# Reed_Switch_Input.net
KiCad netlist of a schematic drawn in Altium Designer
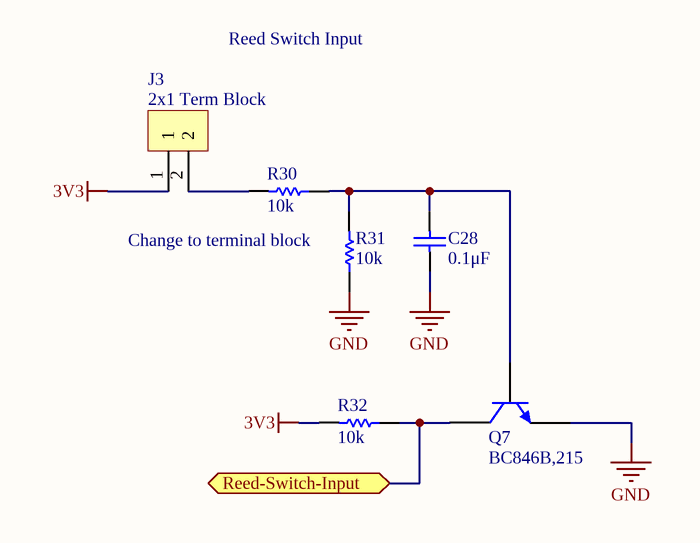
[diagram p0: Reed_Switch_Input.SchDoc]

(export (version "E")
  (design (tool "Eeschema 10.0.6"))
  (components
    (comp (ref "C28")
      (value "0.1μF")
      (footprint "CAPC1608N(0603\")")
      (description "Capacitor, Ceramic, 100V, +/- 10%, 0603 SMD, X7R")
      (fields
        (field (name "MFG") "TDK")
        (field (name "PUBLISHER") "AUVic")
        (field (name "CREATED BY") "Ashwin Sira")
      )
      (libsource (lib "AUVic_Integrated_Library_Capacitors") (part "0.1uF 100V 0603 SMD, Ceramic"))
    )
    (comp (ref "J3")
      (value "2x1 Term Block")
      (footprint "2X1 Terminal Blocks")
      (fields (field (name "MADE BY") "Andy Bates"))
      (libsource (lib "AUVic_Integrated_Library_Connectors") (part "2x1 Terminal Block"))
    )
    (comp (ref "Q7")
      (value "BC846B,215")
      (footprint "SOT-23")
      (description "NPN 65V 100mA 250mW")
      (fields (field (name "PUBLISHER") "Andy Bates"))
      (libsource (lib "AUVic_Integrated_Library_Transistors") (part "BC846B,215"))
    )
    (comp (ref "R30")
      (value "10k")
      (footprint "RESC1608N(0603\")")
      (description "10kR, 1%, 1/10W, 0603 SMD")
      (fields (field (name "MADE BY") "Ashwin Sira"))
      (libsource (lib "AUVic_Integrated_Library_Resistors") (part "10kR, 1%, 1/10W, 0603 SMD"))
    )
    (comp (ref "R31")
      (value "10k")
      (footprint "RESC1608N(0603\")")
      (description "10kR, 1%, 1/10W, 0603 SMD")
      (fields (field (name "MADE BY") "Ashwin Sira"))
      (libsource (lib "AUVic_Integrated_Library_Resistors") (part "10kR, 1%, 1/10W, 0603 SMD"))
    )
    (comp (ref "R32")
      (value "10k")
      (footprint "RESC1608N(0603\")")
      (description "10kR, 1%, 1/10W, 0603 SMD")
      (fields (field (name "MADE BY") "Ashwin Sira"))
      (libsource (lib "AUVic_Integrated_Library_Resistors") (part "10kR, 1%, 1/10W, 0603 SMD"))
    )
  )
  (nets
    (net (code "1") (name "/Reed-Switch-Input") (class "Default")
      (node (ref "Q7") (pin "3") (pinfunction "C_3") (pintype "passive"))
      (node (ref "R32") (pin "1") (pinfunction "1_1") (pintype "passive"))
    )
    (net (code "2") (name "3V3") (class "Default")
      (node (ref "J3") (pin "1") (pinfunction "1_1") (pintype "passive"))
      (node (ref "R32") (pin "2") (pinfunction "2_2") (pintype "passive"))
    )
    (net (code "3") (name "GND") (class "Default")
      (node (ref "C28") (pin "1") (pinfunction "Anode_1") (pintype "passive"))
      (node (ref "Q7") (pin "2") (pinfunction "E_2") (pintype "passive"))
      (node (ref "R31") (pin "1") (pinfunction "1_1") (pintype "passive"))
    )
    (net (code "4") (name "Net-(C28-Cathode)") (class "Default")
      (node (ref "C28") (pin "2") (pinfunction "Cathode_2") (pintype "passive"))
      (node (ref "Q7") (pin "1") (pinfunction "B_1") (pintype "passive"))
      (node (ref "R30") (pin "1") (pinfunction "1_1") (pintype "passive"))
      (node (ref "R31") (pin "2") (pinfunction "2_2") (pintype "passive"))
    )
    (net (code "5") (name "Net-(J3-Pad2)") (class "Default")
      (node (ref "J3") (pin "2") (pinfunction "2_2") (pintype "passive"))
      (node (ref "R30") (pin "2") (pinfunction "2_2") (pintype "passive"))
    )
  )
)
